# ESP8266_Core.net
KiCad netlist of a schematic drawn in Altium Designer
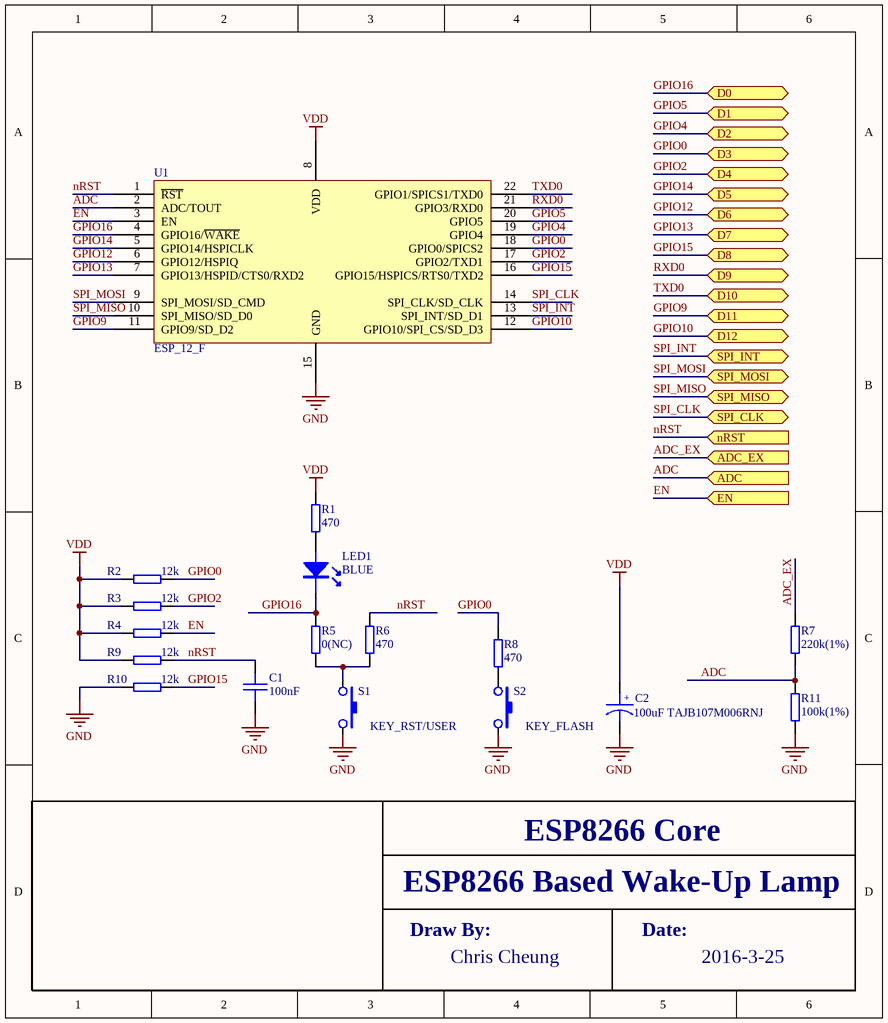
[diagram p0: ESP8266 Core.SchDoc]

(export (version "E")
  (design (tool "Eeschema 10.0.6"))
  (components
    (comp (ref "C1")
      (value "100nF")
      (footprint "SMT_C_0402")
      (description "Surface mount capacitor 0402")
      (libsource (lib "Vowstar_Basic_Device") (part "SMT_C_0402"))
    )
    (comp (ref "C2")
      (value "100uF TAJB107M006RNJ")
      (footprint "SMT_C_Tantalum_B")
      (description "Capacitor, SM Tantalum; Body 3.5 x 2.8 mm (LxW typ)")
      (libsource (lib "Vowstar_Basic_Device") (part "SMT_C_Tantalum_B"))
    )
    (comp (ref "LED1")
      (value "BLUE")
      (footprint "SMT_LED_0603")
      (description "SMT LED")
      (libsource (lib "Vowstar_Basic_Device") (part "SMT_LED_0603"))
    )
    (comp (ref "R1")
      (value "470")
      (footprint "SMT_R_0402")
      (description "Surface mount resistor 0402")
      (libsource (lib "Vowstar_Basic_Device") (part "SMT_R_0402"))
    )
    (comp (ref "R2")
      (value "12k")
      (footprint "SMT_R_0402")
      (description "Surface mount resistor 0402")
      (libsource (lib "Vowstar_Basic_Device") (part "SMT_R_0402"))
    )
    (comp (ref "R3")
      (value "12k")
      (footprint "SMT_R_0402")
      (description "Surface mount resistor 0402")
      (libsource (lib "Vowstar_Basic_Device") (part "SMT_R_0402"))
    )
    (comp (ref "R4")
      (value "12k")
      (footprint "SMT_R_0402")
      (description "Surface mount resistor 0402")
      (libsource (lib "Vowstar_Basic_Device") (part "SMT_R_0402"))
    )
    (comp (ref "R5")
      (value "0(NC)")
      (footprint "SMT_R_0402")
      (description "Surface mount resistor 0402")
      (libsource (lib "Vowstar_Basic_Device") (part "SMT_R_0402"))
    )
    (comp (ref "R6")
      (value "470")
      (footprint "SMT_R_0402")
      (description "Surface mount resistor 0402")
      (libsource (lib "Vowstar_Basic_Device") (part "SMT_R_0402"))
    )
    (comp (ref "R7")
      (value "220k(1%)")
      (footprint "SMT_R_0402")
      (description "Surface mount resistor 0402")
      (libsource (lib "Vowstar_Basic_Device") (part "SMT_R_0402"))
    )
    (comp (ref "R8")
      (value "470")
      (footprint "SMT_R_0402")
      (description "Surface mount resistor 0402")
      (libsource (lib "Vowstar_Basic_Device") (part "SMT_R_0402"))
    )
    (comp (ref "R9")
      (value "12k")
      (footprint "SMT_R_0402")
      (description "Surface mount resistor 0402")
      (libsource (lib "Vowstar_Basic_Device") (part "SMT_R_0402"))
    )
    (comp (ref "R10")
      (value "12k")
      (footprint "SMT_R_0402")
      (description "Surface mount resistor 0402")
      (libsource (lib "Vowstar_Basic_Device") (part "SMT_R_0402"))
    )
    (comp (ref "R11")
      (value "100k(1%)")
      (footprint "SMT_R_0402")
      (description "Surface mount resistor 0402")
      (libsource (lib "Vowstar_Basic_Device") (part "SMT_R_0402"))
    )
    (comp (ref "S1")
      (value "KEY_RST/USER")
      (footprint "SMT_SW_PTS_820")
      (description "SMT Tactile ‎Switch PTS 820 Series")
      (libsource (lib "Vowstar_Switch") (part "SMT_SW_PTS_820"))
    )
    (comp (ref "S2")
      (value "KEY_FLASH")
      (footprint "SMT_SW_PTS_820")
      (description "SMT Tactile ‎Switch PTS 820 Series")
      (libsource (lib "Vowstar_Switch") (part "SMT_SW_PTS_820"))
    )
    (comp (ref "U1")
      (value "ESP_12_F")
      (footprint "ESP_12_E_L")
      (description "ESP-12 Wi-Fi Module by AI-Thinker")
      (libsource (lib "Vowstar_Module") (part "ESP_12_E"))
    )
  )
  (nets
    (net (code "1") (name "/ADC") (class "Default")
      (node (ref "R11") (pin "2") (pinfunction "2_2") (pintype "passive"))
      (node (ref "R7") (pin "1") (pinfunction "1_1") (pintype "passive"))
      (node (ref "U1") (pin "2") (pinfunction "ADC/TOUT_2") (pintype "passive"))
    )
    (net (code "2") (name "/ADC_EX") (class "Default")
      (node (ref "R7") (pin "2") (pinfunction "2_2") (pintype "passive"))
    )
    (net (code "3") (name "/EN") (class "Default")
      (node (ref "R4") (pin "2") (pinfunction "2_2") (pintype "passive"))
      (node (ref "U1") (pin "3") (pinfunction "EN_3") (pintype "passive"))
    )
    (net (code "4") (name "/GPIO0") (class "Default")
      (node (ref "R2") (pin "2") (pinfunction "2_2") (pintype "passive"))
      (node (ref "R8") (pin "2") (pinfunction "2_2") (pintype "passive"))
      (node (ref "U1") (pin "18") (pinfunction "GPIO0/SPICS2_18") (pintype "passive"))
    )
    (net (code "5") (name "/GPIO2") (class "Default")
      (node (ref "R3") (pin "2") (pinfunction "2_2") (pintype "passive"))
      (node (ref "U1") (pin "17") (pinfunction "GPIO2/TXD1_17") (pintype "passive"))
    )
    (net (code "6") (name "/GPIO4") (class "Default")
      (node (ref "U1") (pin "19") (pinfunction "GPIO4_19") (pintype "passive"))
    )
    (net (code "7") (name "/GPIO5") (class "Default")
      (node (ref "U1") (pin "20") (pinfunction "GPIO5_20") (pintype "passive"))
    )
    (net (code "8") (name "/GPIO9") (class "Default")
      (node (ref "U1") (pin "11") (pinfunction "GPIO9/SD_D2_11") (pintype "passive"))
    )
    (net (code "9") (name "/GPIO10") (class "Default")
      (node (ref "U1") (pin "12") (pinfunction "GPIO10/SPI_CS/SD_D3_12") (pintype "passive"))
    )
    (net (code "10") (name "/GPIO12") (class "Default")
      (node (ref "U1") (pin "6") (pinfunction "GPIO12/HSPIQ_6") (pintype "passive"))
    )
    (net (code "11") (name "/GPIO13") (class "Default")
      (node (ref "U1") (pin "7") (pinfunction "GPIO13/HSPID/CTS0/RXD2_7") (pintype "passive"))
    )
    (net (code "12") (name "/GPIO14") (class "Default")
      (node (ref "U1") (pin "5") (pinfunction "GPIO14/HSPICLK_5") (pintype "passive"))
    )
    (net (code "13") (name "/GPIO15") (class "Default")
      (node (ref "R10") (pin "2") (pinfunction "2_2") (pintype "passive"))
      (node (ref "U1") (pin "16") (pinfunction "GPIO15/HSPICS/RTS0/TXD2_16") (pintype "passive"))
    )
    (net (code "14") (name "/GPIO16") (class "Default")
      (node (ref "LED1") (pin "2") (pinfunction "K_2") (pintype "passive"))
      (node (ref "R5") (pin "2") (pinfunction "2_2") (pintype "passive"))
      (node (ref "U1") (pin "4") (pinfunction "GPIO16/~{WAKE}_4") (pintype "passive"))
    )
    (net (code "15") (name "/RXD0") (class "Default")
      (node (ref "U1") (pin "21") (pinfunction "GPIO3/RXD0_21") (pintype "passive"))
    )
    (net (code "16") (name "/SPI_CLK") (class "Default")
      (node (ref "U1") (pin "14") (pinfunction "SPI_CLK/SD_CLK_14") (pintype "passive"))
    )
    (net (code "17") (name "/SPI_INT") (class "Default")
      (node (ref "U1") (pin "13") (pinfunction "SPI_INT/SD_D1_13") (pintype "passive"))
    )
    (net (code "18") (name "/SPI_MISO") (class "Default")
      (node (ref "U1") (pin "10") (pinfunction "SPI_MISO/SD_D0_10") (pintype "passive"))
    )
    (net (code "19") (name "/SPI_MOSI") (class "Default")
      (node (ref "U1") (pin "9") (pinfunction "SPI_MOSI/SD_CMD_9") (pintype "passive"))
    )
    (net (code "20") (name "/TXD0") (class "Default")
      (node (ref "U1") (pin "22") (pinfunction "GPIO1/SPICS1/TXD0_22") (pintype "passive"))
    )
    (net (code "21") (name "/nRST") (class "Default")
      (node (ref "C1") (pin "1") (pinfunction "1_1") (pintype "passive"))
      (node (ref "R6") (pin "2") (pinfunction "2_2") (pintype "passive"))
      (node (ref "R9") (pin "2") (pinfunction "2_2") (pintype "passive"))
      (node (ref "U1") (pin "1") (pinfunction "~{RST}_1") (pintype "passive"))
    )
    (net (code "22") (name "GND") (class "Default")
      (node (ref "C1") (pin "2") (pinfunction "2_2") (pintype "passive"))
      (node (ref "C2") (pin "2") (pinfunction "2_2") (pintype "passive"))
      (node (ref "R10") (pin "1") (pinfunction "1_1") (pintype "passive"))
      (node (ref "R11") (pin "1") (pinfunction "1_1") (pintype "passive"))
      (node (ref "S1") (pin "2") (pinfunction "2_2") (pintype "passive"))
      (node (ref "S2") (pin "2") (pinfunction "2_2") (pintype "passive"))
      (node (ref "U1") (pin "15") (pinfunction "GND_15") (pintype "passive"))
    )
    (net (code "23") (name "Net-(LED1-A)") (class "Default")
      (node (ref "LED1") (pin "1") (pinfunction "A_1") (pintype "passive"))
      (node (ref "R1") (pin "1") (pinfunction "1_1") (pintype "passive"))
    )
    (net (code "24") (name "Net-(R5-Pad1)") (class "Default")
      (node (ref "R5") (pin "1") (pinfunction "1_1") (pintype "passive"))
      (node (ref "R6") (pin "1") (pinfunction "1_1") (pintype "passive"))
      (node (ref "S1") (pin "1") (pinfunction "1_1") (pintype "passive"))
    )
    (net (code "25") (name "Net-(R8-Pad1)") (class "Default")
      (node (ref "R8") (pin "1") (pinfunction "1_1") (pintype "passive"))
      (node (ref "S2") (pin "1") (pinfunction "1_1") (pintype "passive"))
    )
    (net (code "26") (name "VDD") (class "Default")
      (node (ref "C2") (pin "1") (pinfunction "1_1") (pintype "passive"))
      (node (ref "R1") (pin "2") (pinfunction "2_2") (pintype "passive"))
      (node (ref "R2") (pin "1") (pinfunction "1_1") (pintype "passive"))
      (node (ref "R3") (pin "1") (pinfunction "1_1") (pintype "passive"))
      (node (ref "R4") (pin "1") (pinfunction "1_1") (pintype "passive"))
      (node (ref "R9") (pin "1") (pinfunction "1_1") (pintype "passive"))
      (node (ref "U1") (pin "8") (pinfunction "VDD_8") (pintype "passive"))
    )
  )
)
